# test1_2sch.net
KiCad netlist of a schematic drawn in EAGLE
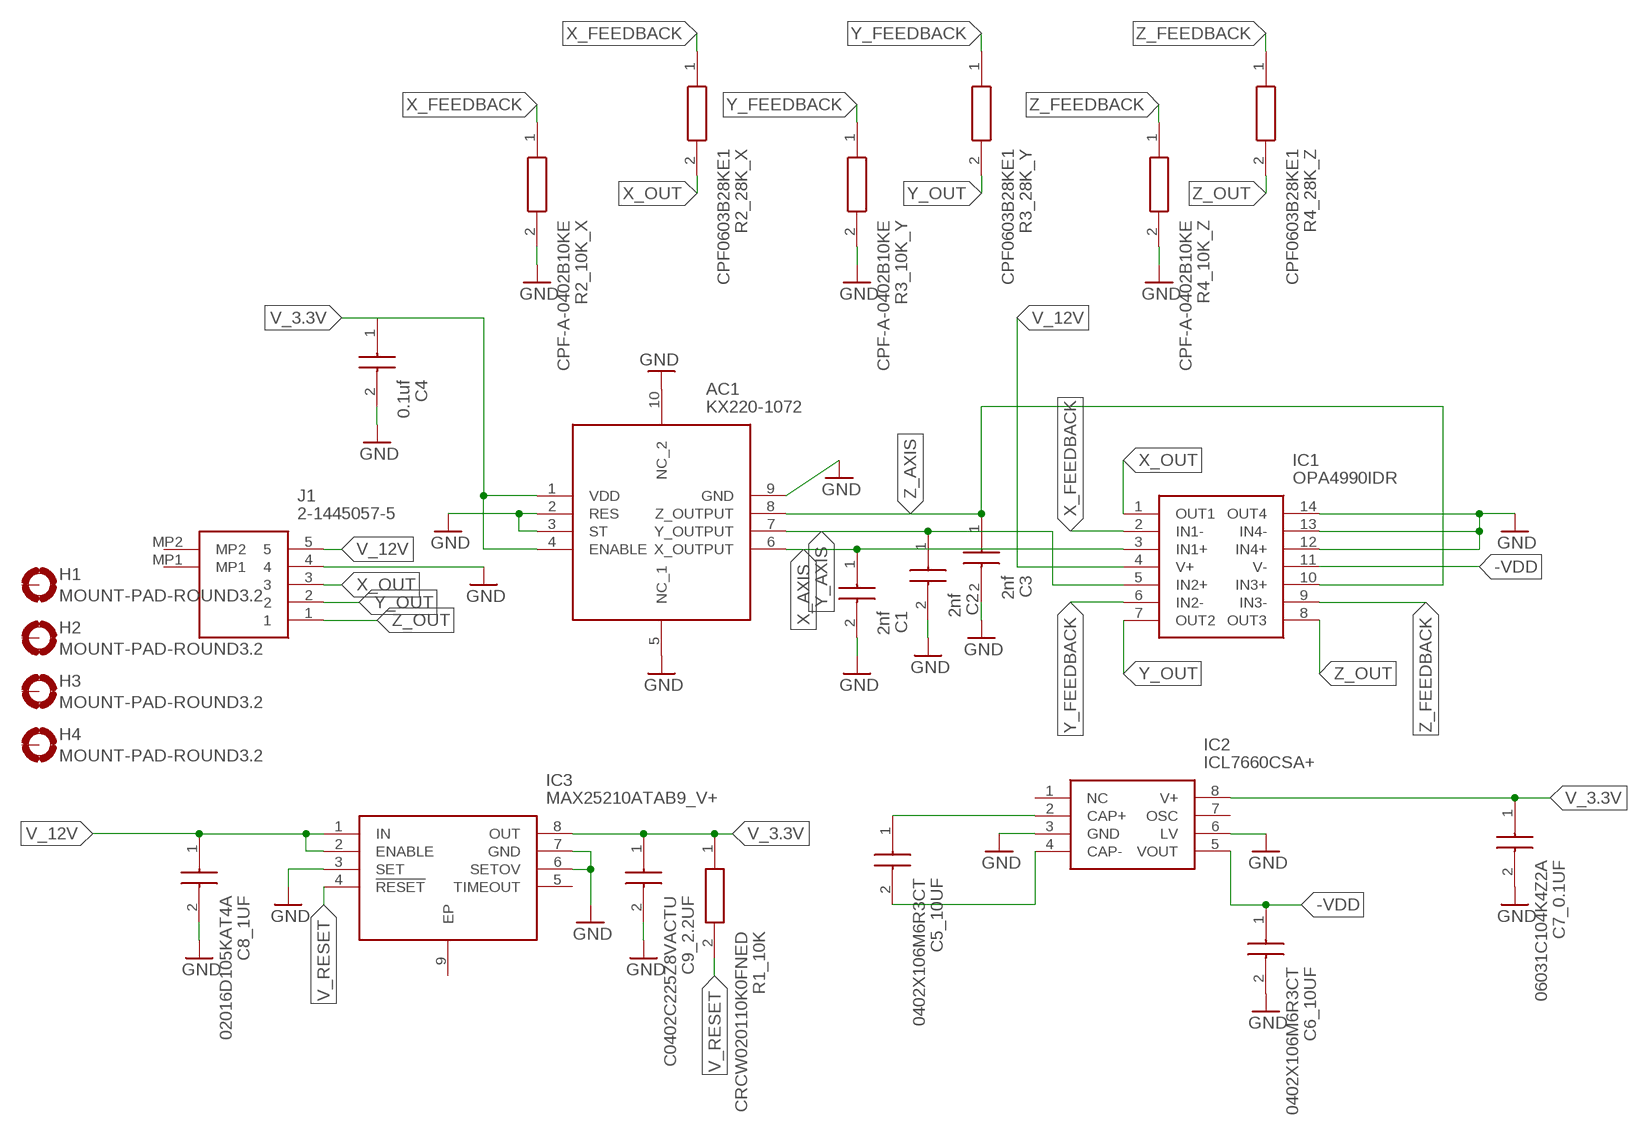
[diagram p0: schematic, sheet 1]

(export (version "E")
  (design (tool "Eeschema 10.0.6"))
  (components
    (comp (ref "AC1")
      (value "KX220-1072")
      (footprint "eagle-import:KX2201072")
      (fields (field (name "MOUSER_PART_NUMBER") "912-KX220-1072"))
      (libsource (lib "eagle-import") (part "KX220-1072"))
    )
    (comp (ref "C1")
      (value "2nf")
      (footprint "eagle-import:CAPC1005X60N")
      (fields
        (field (name "MANUFACTURER_PART_NUMBER") "C0402C202J3GACTU")
        (field (name "MOUSER_PART_NUMBER") "80-C0402C202J3G")
      )
      (libsource (lib "eagle-import") (part "C0402C202J3GACTU"))
    )
    (comp (ref "C2")
      (value "2nf")
      (footprint "eagle-import:CAPC1005X60N")
      (fields
        (field (name "MANUFACTURER_PART_NUMBER") "C0402C202J3GACTU")
        (field (name "MOUSER_PART_NUMBER") "80-C0402C202J3G")
      )
      (libsource (lib "eagle-import") (part "C0402C202J3GACTU"))
    )
    (comp (ref "C3")
      (value "2nf")
      (footprint "eagle-import:CAPC1005X60N")
      (fields
        (field (name "MANUFACTURER_PART_NUMBER") "C0402C202J3GACTU")
        (field (name "MOUSER_PART_NUMBER") "80-C0402C202J3G")
      )
      (libsource (lib "eagle-import") (part "C0402C202J3GACTU"))
    )
    (comp (ref "C4")
      (value "0.1uf")
      (footprint "eagle-import:CAPC1608X90N")
      (fields
        (field (name "MANUFACTURER_PART_NUMBER") "06031C104K4Z2A")
        (field (name "MOUSER_PART_NUMBER") "581-06031C104K4Z2A")
      )
      (libsource (lib "eagle-import") (part "06031C104K4Z2A"))
    )
    (comp (ref "C5_10UF")
      (value "0402X106M6R3CT")
      (footprint "eagle-import:CAPC1005X55N")
      (fields (field (name "MOUSER_PART_NUMBER") "791-0402X106M6R3CT"))
      (libsource (lib "eagle-import") (part "0402X106M6R3CT"))
    )
    (comp (ref "C6_10UF")
      (value "0402X106M6R3CT")
      (footprint "eagle-import:CAPC1005X55N")
      (fields (field (name "MOUSER_PART_NUMBER") "791-0402X106M6R3CT"))
      (libsource (lib "eagle-import") (part "0402X106M6R3CT"))
    )
    (comp (ref "C7_0.1UF")
      (value "06031C104K4Z2A")
      (footprint "eagle-import:CAPC1608X90N")
      (fields (field (name "MOUSER_PART_NUMBER") "581-06031C104K4Z2A"))
      (libsource (lib "eagle-import") (part "06031C104K4Z2A"))
    )
    (comp (ref "C8_1UF")
      (value "02016D105KAT4A")
      (footprint "eagle-import:CAPC0603X33N")
      (fields (field (name "MOUSER_PART_NUMBER") "581-02016D105KAT4A"))
      (libsource (lib "eagle-import") (part "02016D105KAT4A"))
    )
    (comp (ref "C9_2.2UF")
      (value "C0402C225Z8VACTU")
      (footprint "eagle-import:INDC1005X55N")
      (fields (field (name "MOUSER_PART_NUMBER") "80-C0402C225Z8VACTU"))
      (libsource (lib "eagle-import") (part "C0402C225Z8VACTU"))
    )
    (comp (ref "H1")
      (value "MOUNT-PAD-ROUND3.2")
      (footprint "eagle-import:3,2-PAD")
      (libsource (lib "eagle-import") (part "MOUNT-PAD-ROUND3.2"))
    )
    (comp (ref "H2")
      (value "MOUNT-PAD-ROUND3.2")
      (footprint "eagle-import:3,2-PAD")
      (libsource (lib "eagle-import") (part "MOUNT-PAD-ROUND3.2"))
    )
    (comp (ref "H3")
      (value "MOUNT-PAD-ROUND3.2")
      (footprint "eagle-import:3,2-PAD")
      (libsource (lib "eagle-import") (part "MOUNT-PAD-ROUND3.2"))
    )
    (comp (ref "H4")
      (value "MOUNT-PAD-ROUND3.2")
      (footprint "eagle-import:3,2-PAD")
      (libsource (lib "eagle-import") (part "MOUNT-PAD-ROUND3.2"))
    )
    (comp (ref "IC1")
      (value "OPA4990IDR")
      (footprint "eagle-import:SOIC127P600X175-14N")
      (fields (field (name "MOUSER_PART_NUMBER") "595-OPA4990IDR"))
      (libsource (lib "eagle-import") (part "OPA4990IDR"))
    )
    (comp (ref "IC2")
      (value "ICL7660CSA+")
      (footprint "eagle-import:SOIC127P600X175-8N")
      (fields (field (name "MOUSER_PART_NUMBER") "700-ICL7660CSA"))
      (libsource (lib "eagle-import") (part "ICL7660CSA+"))
    )
    (comp (ref "IC3")
      (value "MAX25210ATAB9_V+")
      (footprint "eagle-import:SON65P300X300X80-9N")
      (fields
        (field (name "MANUFACTURER_PART_NUMBER") "MAX25210ATAB9/V+")
        (field (name "MOUSER_PART_NUMBER") "700-MAX25210ATAB9/V+")
      )
      (libsource (lib "eagle-import") (part "MAX25210ATAB9_V+"))
    )
    (comp (ref "J1")
      (value "2-1445057-5")
      (footprint "eagle-import:214450575")
      (fields (field (name "MOUSER_PART_NUMBER") "571-2-1445057-5"))
      (libsource (lib "eagle-import") (part "2-1445057-5"))
    )
    (comp (ref "R1_10K")
      (value "CRCW020110K0FNED")
      (footprint "eagle-import:RESC0603X28N")
      (fields (field (name "MOUSER_PART_NUMBER") "71-CRCW0201-10K"))
      (libsource (lib "eagle-import") (part "CRCW020110K0FNED"))
    )
    (comp (ref "R2_10K_X")
      (value "CPF-A-0402B10KE")
      (footprint "eagle-import:RESC1005X35N")
      (fields (field (name "MOUSER_PART_NUMBER") "279-CPF-A-0402B10KE"))
      (libsource (lib "eagle-import") (part "CPF-A-0402B10KE"))
    )
    (comp (ref "R2_28K_X")
      (value "CPF0603B28KE1")
      (footprint "eagle-import:RESC1608X55N")
      (libsource (lib "eagle-import") (part "CPF0603B28KE1"))
    )
    (comp (ref "R3_10K_Y")
      (value "CPF-A-0402B10KE")
      (footprint "eagle-import:RESC1005X35N")
      (fields (field (name "MOUSER_PART_NUMBER") "279-CPF-A-0402B10KE"))
      (libsource (lib "eagle-import") (part "CPF-A-0402B10KE"))
    )
    (comp (ref "R3_28K_Y")
      (value "CPF0603B28KE1")
      (footprint "eagle-import:RESC1608X55N")
      (libsource (lib "eagle-import") (part "CPF0603B28KE1"))
    )
    (comp (ref "R4_10K_Z")
      (value "CPF-A-0402B10KE")
      (footprint "eagle-import:RESC1005X35N")
      (fields (field (name "MOUSER_PART_NUMBER") "279-CPF-A-0402B10KE"))
      (libsource (lib "eagle-import") (part "CPF-A-0402B10KE"))
    )
    (comp (ref "R4_28K_Z")
      (value "CPF0603B28KE1")
      (footprint "eagle-import:RESC1608X55N")
      (libsource (lib "eagle-import") (part "CPF0603B28KE1"))
    )
  )
  (nets
    (net (code "1") (name "-VDD") (class "Default")
      (node (ref "C6_10UF") (pin "1") (pinfunction "1_1") (pintype "bidirectional"))
      (node (ref "IC1") (pin "11") (pinfunction "V-_11") (pintype "bidirectional"))
      (node (ref "IC2") (pin "5") (pinfunction "VOUT_5") (pintype "bidirectional"))
    )
    (net (code "2") (name "GND") (class "Default")
      (node (ref "AC1") (pin "10") (pinfunction "NC_2_10") (pintype "bidirectional"))
      (node (ref "AC1") (pin "2") (pinfunction "RES_2") (pintype "bidirectional"))
      (node (ref "AC1") (pin "3") (pinfunction "ST_3") (pintype "bidirectional"))
      (node (ref "AC1") (pin "5") (pinfunction "NC_1_5") (pintype "bidirectional"))
      (node (ref "AC1") (pin "9") (pinfunction "GND_9") (pintype "bidirectional"))
      (node (ref "C1") (pin "2") (pinfunction "C2_2") (pintype "bidirectional"))
      (node (ref "C2") (pin "2") (pinfunction "C2_2") (pintype "bidirectional"))
      (node (ref "C3") (pin "2") (pinfunction "C2_2") (pintype "bidirectional"))
      (node (ref "C4") (pin "2") (pinfunction "2_2") (pintype "bidirectional"))
      (node (ref "C6_10UF") (pin "2") (pinfunction "2_2") (pintype "bidirectional"))
      (node (ref "C7_0.1UF") (pin "2") (pinfunction "2_2") (pintype "bidirectional"))
      (node (ref "C8_1UF") (pin "2") (pinfunction "2_2") (pintype "bidirectional"))
      (node (ref "C9_2.2UF") (pin "2") (pinfunction "2_2") (pintype "bidirectional"))
      (node (ref "IC1") (pin "12") (pinfunction "IN4+_12") (pintype "bidirectional"))
      (node (ref "IC1") (pin "13") (pinfunction "IN4-_13") (pintype "bidirectional"))
      (node (ref "IC1") (pin "14") (pinfunction "OUT4_14") (pintype "bidirectional"))
      (node (ref "IC2") (pin "3") (pinfunction "GND_3") (pintype "bidirectional"))
      (node (ref "IC2") (pin "6") (pinfunction "LV_6") (pintype "bidirectional"))
      (node (ref "IC3") (pin "3") (pinfunction "SET_3") (pintype "bidirectional"))
      (node (ref "IC3") (pin "6") (pinfunction "SETOV_6") (pintype "bidirectional"))
      (node (ref "IC3") (pin "7") (pinfunction "GND_7") (pintype "bidirectional"))
      (node (ref "J1") (pin "4") (pinfunction "4_4") (pintype "bidirectional"))
      (node (ref "R2_10K_X") (pin "2") (pinfunction "2_2") (pintype "bidirectional"))
      (node (ref "R3_10K_Y") (pin "2") (pinfunction "2_2") (pintype "bidirectional"))
      (node (ref "R4_10K_Z") (pin "2") (pinfunction "2_2") (pintype "bidirectional"))
    )
    (net (code "3") (name "Net-(IC2-CAP+)") (class "Default")
      (node (ref "C5_10UF") (pin "1") (pinfunction "1_1") (pintype "bidirectional"))
      (node (ref "IC2") (pin "2") (pinfunction "CAP+_2") (pintype "bidirectional"))
    )
    (net (code "4") (name "Net-(IC2-CAP-)") (class "Default")
      (node (ref "C5_10UF") (pin "2") (pinfunction "2_2") (pintype "bidirectional"))
      (node (ref "IC2") (pin "4") (pinfunction "CAP-_4") (pintype "bidirectional"))
    )
    (net (code "5") (name "V_3.3V") (class "Default")
      (node (ref "AC1") (pin "1") (pinfunction "VDD_1") (pintype "bidirectional"))
      (node (ref "AC1") (pin "4") (pinfunction "ENABLE_4") (pintype "bidirectional"))
      (node (ref "C4") (pin "1") (pinfunction "1_1") (pintype "bidirectional"))
      (node (ref "C7_0.1UF") (pin "1") (pinfunction "1_1") (pintype "bidirectional"))
      (node (ref "C9_2.2UF") (pin "1") (pinfunction "1_1") (pintype "bidirectional"))
      (node (ref "IC2") (pin "8") (pinfunction "V+_8") (pintype "bidirectional"))
      (node (ref "IC3") (pin "8") (pinfunction "OUT_8") (pintype "bidirectional"))
      (node (ref "R1_10K") (pin "1") (pinfunction "1_1") (pintype "bidirectional"))
    )
    (net (code "6") (name "V_12V") (class "Default")
      (node (ref "C8_1UF") (pin "1") (pinfunction "1_1") (pintype "bidirectional"))
      (node (ref "IC1") (pin "4") (pinfunction "V+_4") (pintype "bidirectional"))
      (node (ref "IC3") (pin "1") (pinfunction "IN_1") (pintype "bidirectional"))
      (node (ref "IC3") (pin "2") (pinfunction "ENABLE_2") (pintype "bidirectional"))
      (node (ref "J1") (pin "5") (pinfunction "5_5") (pintype "bidirectional"))
    )
    (net (code "7") (name "V_RESET") (class "Default")
      (node (ref "IC3") (pin "4") (pinfunction "~{RESET}_4") (pintype "bidirectional"))
      (node (ref "R1_10K") (pin "2") (pinfunction "2_2") (pintype "bidirectional"))
    )
    (net (code "8") (name "X_AXIS") (class "Default")
      (node (ref "AC1") (pin "6") (pinfunction "X_OUTPUT_6") (pintype "bidirectional"))
      (node (ref "C1") (pin "1") (pinfunction "C1_1") (pintype "bidirectional"))
      (node (ref "IC1") (pin "3") (pinfunction "IN1+_3") (pintype "bidirectional"))
    )
    (net (code "9") (name "X_FEEDBACK") (class "Default")
      (node (ref "IC1") (pin "2") (pinfunction "IN1-_2") (pintype "bidirectional"))
      (node (ref "R2_10K_X") (pin "1") (pinfunction "1_1") (pintype "bidirectional"))
      (node (ref "R2_28K_X") (pin "1") (pinfunction "1_1") (pintype "bidirectional"))
    )
    (net (code "10") (name "X_OUT") (class "Default")
      (node (ref "IC1") (pin "1") (pinfunction "OUT1_1") (pintype "bidirectional"))
      (node (ref "J1") (pin "3") (pinfunction "3_3") (pintype "bidirectional"))
      (node (ref "R2_28K_X") (pin "2") (pinfunction "2_2") (pintype "bidirectional"))
    )
    (net (code "11") (name "Y_AXIS") (class "Default")
      (node (ref "AC1") (pin "7") (pinfunction "Y_OUTPUT_7") (pintype "bidirectional"))
      (node (ref "C2") (pin "1") (pinfunction "C1_1") (pintype "bidirectional"))
      (node (ref "IC1") (pin "5") (pinfunction "IN2+_5") (pintype "bidirectional"))
    )
    (net (code "12") (name "Y_FEEDBACK") (class "Default")
      (node (ref "IC1") (pin "6") (pinfunction "IN2-_6") (pintype "bidirectional"))
      (node (ref "R3_10K_Y") (pin "1") (pinfunction "1_1") (pintype "bidirectional"))
      (node (ref "R3_28K_Y") (pin "1") (pinfunction "1_1") (pintype "bidirectional"))
    )
    (net (code "13") (name "Y_OUT") (class "Default")
      (node (ref "IC1") (pin "7") (pinfunction "OUT2_7") (pintype "bidirectional"))
      (node (ref "J1") (pin "2") (pinfunction "2_2") (pintype "bidirectional"))
      (node (ref "R3_28K_Y") (pin "2") (pinfunction "2_2") (pintype "bidirectional"))
    )
    (net (code "14") (name "Z_AXIS") (class "Default")
      (node (ref "AC1") (pin "8") (pinfunction "Z_OUTPUT_8") (pintype "bidirectional"))
      (node (ref "C3") (pin "1") (pinfunction "C1_1") (pintype "bidirectional"))
      (node (ref "IC1") (pin "10") (pinfunction "IN3+_10") (pintype "bidirectional"))
    )
    (net (code "15") (name "Z_FEEDBACK") (class "Default")
      (node (ref "IC1") (pin "9") (pinfunction "IN3-_9") (pintype "bidirectional"))
      (node (ref "R4_10K_Z") (pin "1") (pinfunction "1_1") (pintype "bidirectional"))
      (node (ref "R4_28K_Z") (pin "1") (pinfunction "1_1") (pintype "bidirectional"))
    )
    (net (code "16") (name "Z_OUT") (class "Default")
      (node (ref "IC1") (pin "8") (pinfunction "OUT3_8") (pintype "bidirectional"))
      (node (ref "J1") (pin "1") (pinfunction "1_1") (pintype "bidirectional"))
      (node (ref "R4_28K_Z") (pin "2") (pinfunction "2_2") (pintype "bidirectional"))
    )
    (net (code "17") (name "unconnected-(H1-MOUNT-PadB3,2)") (class "Default")
      (node (ref "H1") (pin "B3,2") (pinfunction "MOUNT_B3,2") (pintype "passive"))
    )
    (net (code "18") (name "unconnected-(H2-MOUNT-PadB3,2)") (class "Default")
      (node (ref "H2") (pin "B3,2") (pinfunction "MOUNT_B3,2") (pintype "passive"))
    )
    (net (code "19") (name "unconnected-(H3-MOUNT-PadB3,2)") (class "Default")
      (node (ref "H3") (pin "B3,2") (pinfunction "MOUNT_B3,2") (pintype "passive"))
    )
    (net (code "20") (name "unconnected-(H4-MOUNT-PadB3,2)") (class "Default")
      (node (ref "H4") (pin "B3,2") (pinfunction "MOUNT_B3,2") (pintype "passive"))
    )
    (net (code "21") (name "unconnected-(IC2-NC-Pad1)") (class "Default")
      (node (ref "IC2") (pin "1") (pinfunction "NC_1") (pintype "no_connect"))
    )
    (net (code "22") (name "unconnected-(IC2-OSC-Pad7)") (class "Default")
      (node (ref "IC2") (pin "7") (pinfunction "OSC_7") (pintype "bidirectional"))
    )
    (net (code "23") (name "unconnected-(IC3-EP-Pad9)") (class "Default")
      (node (ref "IC3") (pin "9") (pinfunction "EP_9") (pintype "bidirectional"))
    )
    (net (code "24") (name "unconnected-(IC3-TIMEOUT-Pad5)") (class "Default")
      (node (ref "IC3") (pin "5") (pinfunction "TIMEOUT_5") (pintype "bidirectional"))
    )
    (net (code "25") (name "unconnected-(J1-PadMP1)") (class "Default")
      (node (ref "J1") (pin "MP1") (pinfunction "MP1_MP1") (pintype "bidirectional"))
    )
    (net (code "26") (name "unconnected-(J1-PadMP2)") (class "Default")
      (node (ref "J1") (pin "MP2") (pinfunction "MP2_MP2") (pintype "bidirectional"))
    )
  )
)
